# cell_sense_tht.net
KiCad netlist of a schematic drawn in EAGLE
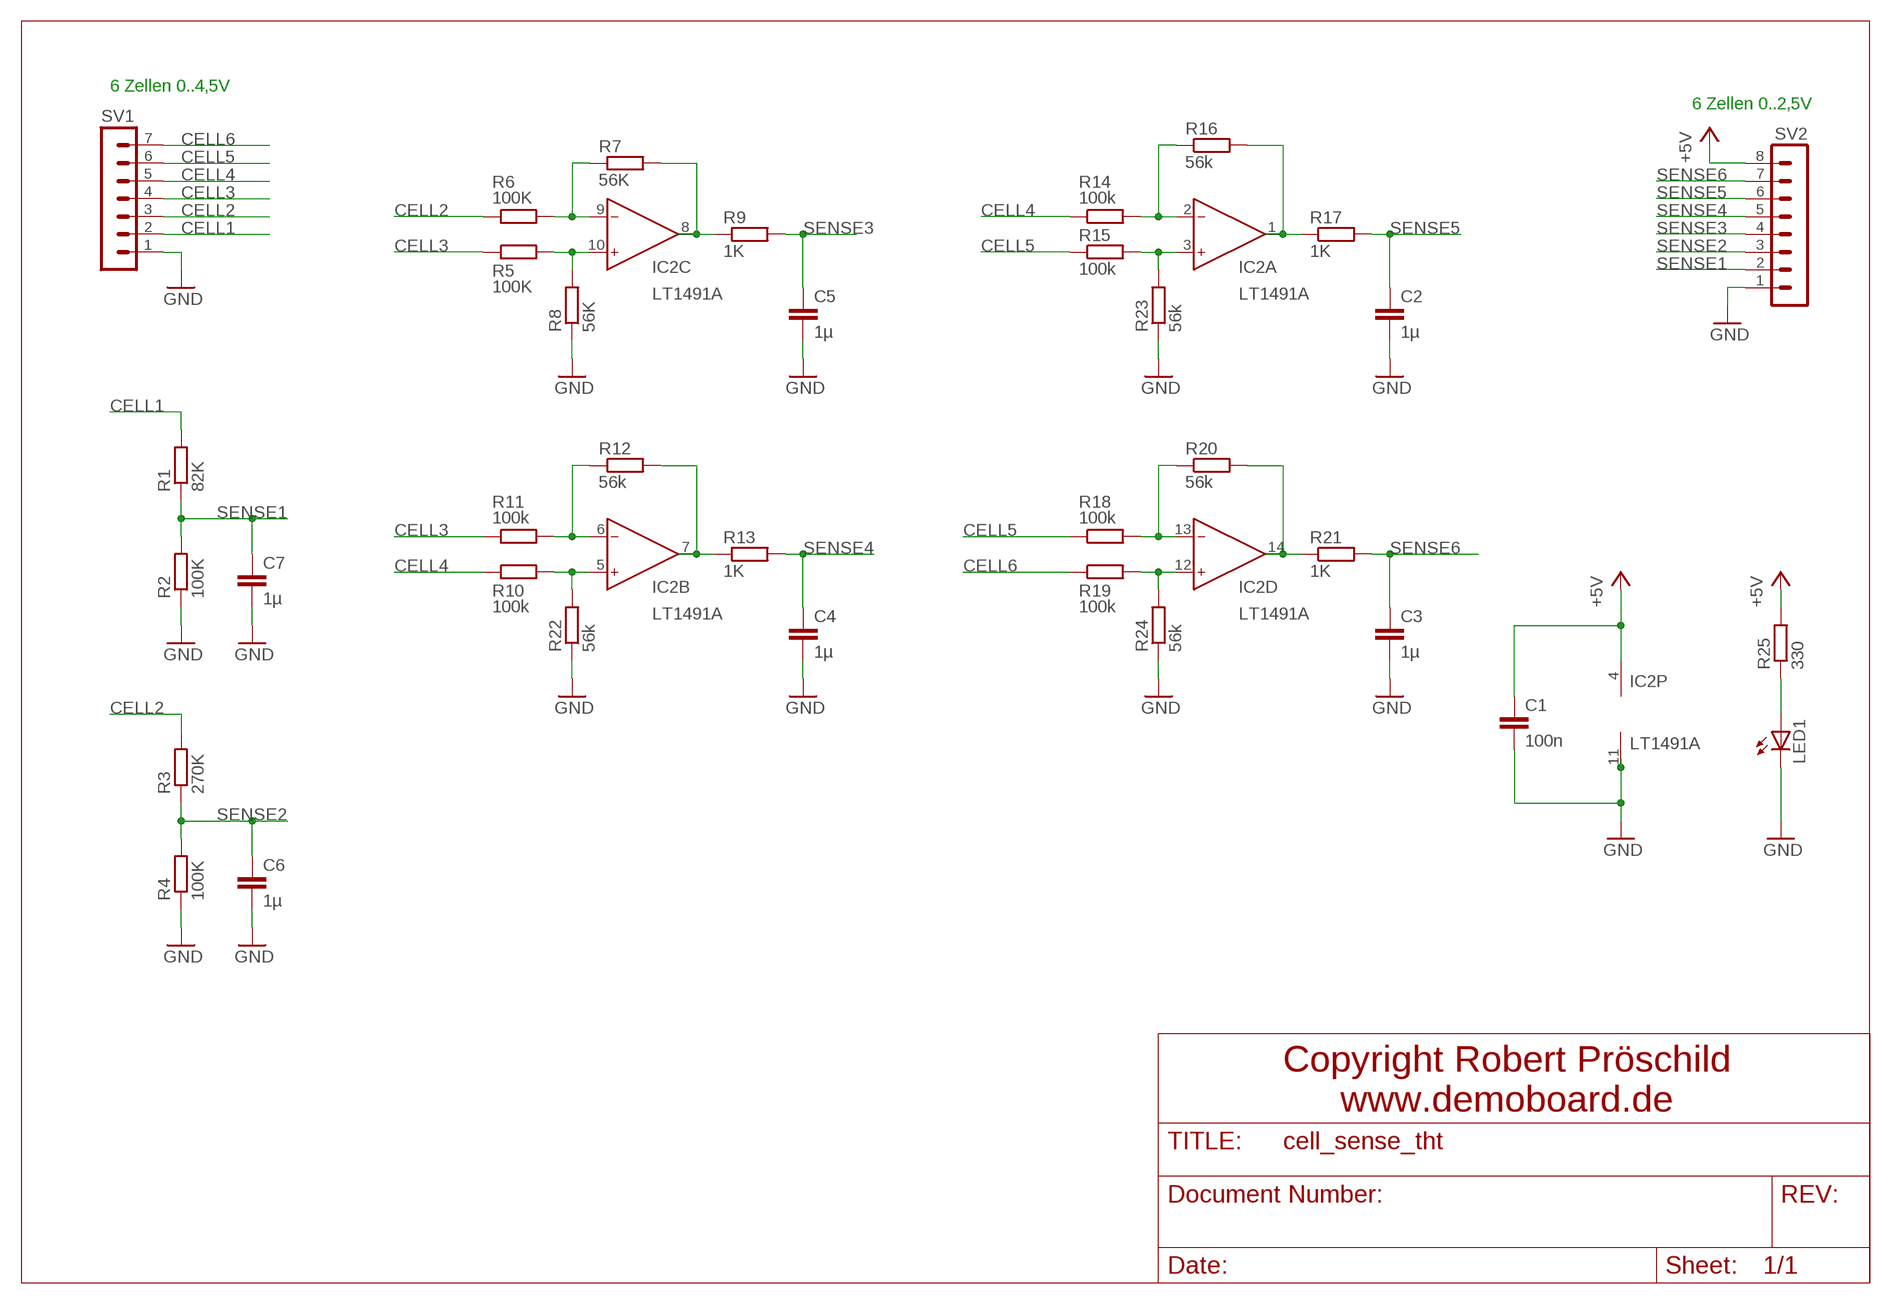
[diagram p0: schematic, sheet 1]

(export (version "E")
  (design (tool "Eeschema 10.0.6"))
  (components
    (comp (ref "C1")
      (value "100n")
      (footprint "eagle-import:C025-024X044")
      (libsource (lib "eagle-import") (part "C-EU025-024X044"))
    )
    (comp (ref "C2")
      (value "1µ")
      (footprint "eagle-import:C025-024X044")
      (libsource (lib "eagle-import") (part "C-EU025-024X044"))
    )
    (comp (ref "C3")
      (value "1µ")
      (footprint "eagle-import:C025-024X044")
      (libsource (lib "eagle-import") (part "C-EU025-024X044"))
    )
    (comp (ref "C4")
      (value "1µ")
      (footprint "eagle-import:C025-024X044")
      (libsource (lib "eagle-import") (part "C-EU025-024X044"))
    )
    (comp (ref "C5")
      (value "1µ")
      (footprint "eagle-import:C025-024X044")
      (libsource (lib "eagle-import") (part "C-EU025-024X044"))
    )
    (comp (ref "C6")
      (value "1µ")
      (footprint "eagle-import:C025-024X044")
      (libsource (lib "eagle-import") (part "C-EU025-024X044"))
    )
    (comp (ref "C7")
      (value "1µ")
      (footprint "eagle-import:C025-024X044")
      (libsource (lib "eagle-import") (part "C-EU025-024X044"))
    )
    (comp (ref "IC2")
      (value "LT1491A")
      (footprint "eagle-import:DIL14")
      (libsource (lib "eagle-import") (part "AD8644"))
    )
    (comp (ref "LED1")
      (value "LED3MM")
      (footprint "eagle-import:LED3MM")
      (libsource (lib "eagle-import") (part "LED3MM"))
    )
    (comp (ref "R1")
      (value "82K")
      (footprint "eagle-import:0204_7")
      (libsource (lib "eagle-import") (part "R-EU_0204/7"))
    )
    (comp (ref "R2")
      (value "100K")
      (footprint "eagle-import:0204_7")
      (libsource (lib "eagle-import") (part "R-EU_0204/7"))
    )
    (comp (ref "R3")
      (value "270K")
      (footprint "eagle-import:0204_7")
      (libsource (lib "eagle-import") (part "R-EU_0204/7"))
    )
    (comp (ref "R4")
      (value "100K")
      (footprint "eagle-import:0204_7")
      (libsource (lib "eagle-import") (part "R-EU_0204/7"))
    )
    (comp (ref "R5")
      (value "100K")
      (footprint "eagle-import:0204_7")
      (libsource (lib "eagle-import") (part "R-EU_0204/7"))
    )
    (comp (ref "R6")
      (value "100K")
      (footprint "eagle-import:0204_7")
      (libsource (lib "eagle-import") (part "R-EU_0204/7"))
    )
    (comp (ref "R7")
      (value "56K")
      (footprint "eagle-import:0204_7")
      (libsource (lib "eagle-import") (part "R-EU_0204/7"))
    )
    (comp (ref "R8")
      (value "56K")
      (footprint "eagle-import:0204_7")
      (libsource (lib "eagle-import") (part "R-EU_0204/7"))
    )
    (comp (ref "R9")
      (value "1K")
      (footprint "eagle-import:0204_7")
      (libsource (lib "eagle-import") (part "R-EU_0204/7"))
    )
    (comp (ref "R10")
      (value "100k")
      (footprint "eagle-import:0204_7")
      (libsource (lib "eagle-import") (part "R-EU_0204/7"))
    )
    (comp (ref "R11")
      (value "100k")
      (footprint "eagle-import:0204_7")
      (libsource (lib "eagle-import") (part "R-EU_0204/7"))
    )
    (comp (ref "R12")
      (value "56k")
      (footprint "eagle-import:0204_7")
      (libsource (lib "eagle-import") (part "R-EU_0204/7"))
    )
    (comp (ref "R13")
      (value "1K")
      (footprint "eagle-import:0204_7")
      (libsource (lib "eagle-import") (part "R-EU_0204/7"))
    )
    (comp (ref "R14")
      (value "100k")
      (footprint "eagle-import:0204_7")
      (libsource (lib "eagle-import") (part "R-EU_0204/7"))
    )
    (comp (ref "R15")
      (value "100k")
      (footprint "eagle-import:0204_7")
      (libsource (lib "eagle-import") (part "R-EU_0204/7"))
    )
    (comp (ref "R16")
      (value "56k")
      (footprint "eagle-import:0204_7")
      (libsource (lib "eagle-import") (part "R-EU_0204/7"))
    )
    (comp (ref "R17")
      (value "1K")
      (footprint "eagle-import:0204_7")
      (libsource (lib "eagle-import") (part "R-EU_0204/7"))
    )
    (comp (ref "R18")
      (value "100k")
      (footprint "eagle-import:0204_7")
      (libsource (lib "eagle-import") (part "R-EU_0204/7"))
    )
    (comp (ref "R19")
      (value "100k")
      (footprint "eagle-import:0204_7")
      (libsource (lib "eagle-import") (part "R-EU_0204/7"))
    )
    (comp (ref "R20")
      (value "56k")
      (footprint "eagle-import:0204_7")
      (libsource (lib "eagle-import") (part "R-EU_0204/7"))
    )
    (comp (ref "R21")
      (value "1K")
      (footprint "eagle-import:0204_7")
      (libsource (lib "eagle-import") (part "R-EU_0204/7"))
    )
    (comp (ref "R22")
      (value "56k")
      (footprint "eagle-import:0204_7")
      (libsource (lib "eagle-import") (part "R-EU_0204/7"))
    )
    (comp (ref "R23")
      (value "56k")
      (footprint "eagle-import:0204_7")
      (libsource (lib "eagle-import") (part "R-EU_0204/7"))
    )
    (comp (ref "R24")
      (value "56k")
      (footprint "eagle-import:0204_7")
      (libsource (lib "eagle-import") (part "R-EU_0204/7"))
    )
    (comp (ref "R25")
      (value "330")
      (footprint "eagle-import:0204_7")
      (libsource (lib "eagle-import") (part "R-EU_0204/7"))
    )
    (comp (ref "SV1")
      (value "MA07-1")
      (footprint "eagle-import:MA07-1")
      (libsource (lib "eagle-import") (part "MA07-1"))
    )
    (comp (ref "SV2")
      (value "MA08-1")
      (footprint "eagle-import:MA08-1")
      (libsource (lib "eagle-import") (part "MA08-1"))
    )
  )
  (nets
    (net (code "1") (name "+5V") (class "Default")
      (node (ref "C1") (pin "1") (pinfunction "1_1") (pintype "passive"))
      (node (ref "IC2") (pin "4") (pinfunction "V+_4") (pintype "power_in"))
      (node (ref "R25") (pin "2") (pinfunction "2_2") (pintype "passive"))
      (node (ref "SV2") (pin "8") (pinfunction "8_8") (pintype "passive"))
    )
    (net (code "2") (name "/CELL1") (class "Default")
      (node (ref "R1") (pin "2") (pinfunction "2_2") (pintype "passive"))
      (node (ref "SV1") (pin "2") (pinfunction "2_2") (pintype "passive"))
    )
    (net (code "3") (name "/CELL2") (class "Default")
      (node (ref "R3") (pin "2") (pinfunction "2_2") (pintype "passive"))
      (node (ref "R6") (pin "1") (pinfunction "1_1") (pintype "passive"))
      (node (ref "SV1") (pin "3") (pinfunction "3_3") (pintype "passive"))
    )
    (net (code "4") (name "/CELL3") (class "Default")
      (node (ref "R11") (pin "1") (pinfunction "1_1") (pintype "passive"))
      (node (ref "R5") (pin "1") (pinfunction "1_1") (pintype "passive"))
      (node (ref "SV1") (pin "4") (pinfunction "4_4") (pintype "passive"))
    )
    (net (code "5") (name "/CELL4") (class "Default")
      (node (ref "R10") (pin "1") (pinfunction "1_1") (pintype "passive"))
      (node (ref "R14") (pin "1") (pinfunction "1_1") (pintype "passive"))
      (node (ref "SV1") (pin "5") (pinfunction "5_5") (pintype "passive"))
    )
    (net (code "6") (name "/CELL5") (class "Default")
      (node (ref "R15") (pin "1") (pinfunction "1_1") (pintype "passive"))
      (node (ref "R18") (pin "1") (pinfunction "1_1") (pintype "passive"))
      (node (ref "SV1") (pin "6") (pinfunction "6_6") (pintype "passive"))
    )
    (net (code "7") (name "/CELL6") (class "Default")
      (node (ref "R19") (pin "1") (pinfunction "1_1") (pintype "passive"))
      (node (ref "SV1") (pin "7") (pinfunction "7_7") (pintype "passive"))
    )
    (net (code "8") (name "/SENSE1") (class "Default")
      (node (ref "C7") (pin "1") (pinfunction "1_1") (pintype "passive"))
      (node (ref "R1") (pin "1") (pinfunction "1_1") (pintype "passive"))
      (node (ref "R2") (pin "2") (pinfunction "2_2") (pintype "passive"))
      (node (ref "SV2") (pin "2") (pinfunction "2_2") (pintype "passive"))
    )
    (net (code "9") (name "/SENSE2") (class "Default")
      (node (ref "C6") (pin "1") (pinfunction "1_1") (pintype "passive"))
      (node (ref "R3") (pin "1") (pinfunction "1_1") (pintype "passive"))
      (node (ref "R4") (pin "2") (pinfunction "2_2") (pintype "passive"))
      (node (ref "SV2") (pin "3") (pinfunction "3_3") (pintype "passive"))
    )
    (net (code "10") (name "/SENSE3") (class "Default")
      (node (ref "C5") (pin "1") (pinfunction "1_1") (pintype "passive"))
      (node (ref "R9") (pin "2") (pinfunction "2_2") (pintype "passive"))
      (node (ref "SV2") (pin "4") (pinfunction "4_4") (pintype "passive"))
    )
    (net (code "11") (name "/SENSE4") (class "Default")
      (node (ref "C4") (pin "1") (pinfunction "1_1") (pintype "passive"))
      (node (ref "R13") (pin "2") (pinfunction "2_2") (pintype "passive"))
      (node (ref "SV2") (pin "5") (pinfunction "5_5") (pintype "passive"))
    )
    (net (code "12") (name "/SENSE5") (class "Default")
      (node (ref "C2") (pin "1") (pinfunction "1_1") (pintype "passive"))
      (node (ref "R17") (pin "2") (pinfunction "2_2") (pintype "passive"))
      (node (ref "SV2") (pin "6") (pinfunction "6_6") (pintype "passive"))
    )
    (net (code "13") (name "/SENSE6") (class "Default")
      (node (ref "C3") (pin "1") (pinfunction "1_1") (pintype "passive"))
      (node (ref "R21") (pin "2") (pinfunction "2_2") (pintype "passive"))
      (node (ref "SV2") (pin "7") (pinfunction "7_7") (pintype "passive"))
    )
    (net (code "14") (name "GND") (class "Default")
      (node (ref "C1") (pin "2") (pinfunction "2_2") (pintype "passive"))
      (node (ref "C2") (pin "2") (pinfunction "2_2") (pintype "passive"))
      (node (ref "C3") (pin "2") (pinfunction "2_2") (pintype "passive"))
      (node (ref "C4") (pin "2") (pinfunction "2_2") (pintype "passive"))
      (node (ref "C5") (pin "2") (pinfunction "2_2") (pintype "passive"))
      (node (ref "C6") (pin "2") (pinfunction "2_2") (pintype "passive"))
      (node (ref "C7") (pin "2") (pinfunction "2_2") (pintype "passive"))
      (node (ref "IC2") (pin "11") (pinfunction "V-_11") (pintype "power_in"))
      (node (ref "LED1") (pin "K") (pinfunction "C_K") (pintype "passive"))
      (node (ref "R2") (pin "1") (pinfunction "1_1") (pintype "passive"))
      (node (ref "R22") (pin "1") (pinfunction "1_1") (pintype "passive"))
      (node (ref "R23") (pin "1") (pinfunction "1_1") (pintype "passive"))
      (node (ref "R24") (pin "1") (pinfunction "1_1") (pintype "passive"))
      (node (ref "R4") (pin "1") (pinfunction "1_1") (pintype "passive"))
      (node (ref "R8") (pin "1") (pinfunction "1_1") (pintype "passive"))
      (node (ref "SV1") (pin "1") (pinfunction "1_1") (pintype "passive"))
      (node (ref "SV2") (pin "1") (pinfunction "1_1") (pintype "passive"))
    )
    (net (code "15") (name "Net-(IC2A-IN+)") (class "Default")
      (node (ref "IC2") (pin "3") (pinfunction "IN+_3") (pintype "input"))
      (node (ref "R15") (pin "2") (pinfunction "2_2") (pintype "passive"))
      (node (ref "R23") (pin "2") (pinfunction "2_2") (pintype "passive"))
    )
    (net (code "16") (name "Net-(IC2A-IN-)") (class "Default")
      (node (ref "IC2") (pin "2") (pinfunction "IN-_2") (pintype "input"))
      (node (ref "R14") (pin "2") (pinfunction "2_2") (pintype "passive"))
      (node (ref "R16") (pin "1") (pinfunction "1_1") (pintype "passive"))
    )
    (net (code "17") (name "Net-(IC2A-OUT)") (class "Default")
      (node (ref "IC2") (pin "1") (pinfunction "OUT_1") (pintype "output"))
      (node (ref "R16") (pin "2") (pinfunction "2_2") (pintype "passive"))
      (node (ref "R17") (pin "1") (pinfunction "1_1") (pintype "passive"))
    )
    (net (code "18") (name "Net-(IC2B-IN+)") (class "Default")
      (node (ref "IC2") (pin "5") (pinfunction "IN+_5") (pintype "input"))
      (node (ref "R10") (pin "2") (pinfunction "2_2") (pintype "passive"))
      (node (ref "R22") (pin "2") (pinfunction "2_2") (pintype "passive"))
    )
    (net (code "19") (name "Net-(IC2B-IN-)") (class "Default")
      (node (ref "IC2") (pin "6") (pinfunction "IN-_6") (pintype "input"))
      (node (ref "R11") (pin "2") (pinfunction "2_2") (pintype "passive"))
      (node (ref "R12") (pin "1") (pinfunction "1_1") (pintype "passive"))
    )
    (net (code "20") (name "Net-(IC2B-OUT)") (class "Default")
      (node (ref "IC2") (pin "7") (pinfunction "OUT_7") (pintype "output"))
      (node (ref "R12") (pin "2") (pinfunction "2_2") (pintype "passive"))
      (node (ref "R13") (pin "1") (pinfunction "1_1") (pintype "passive"))
    )
    (net (code "21") (name "Net-(IC2C-IN+)") (class "Default")
      (node (ref "IC2") (pin "10") (pinfunction "IN+_10") (pintype "input"))
      (node (ref "R5") (pin "2") (pinfunction "2_2") (pintype "passive"))
      (node (ref "R8") (pin "2") (pinfunction "2_2") (pintype "passive"))
    )
    (net (code "22") (name "Net-(IC2C-IN-)") (class "Default")
      (node (ref "IC2") (pin "9") (pinfunction "IN-_9") (pintype "input"))
      (node (ref "R6") (pin "2") (pinfunction "2_2") (pintype "passive"))
      (node (ref "R7") (pin "1") (pinfunction "1_1") (pintype "passive"))
    )
    (net (code "23") (name "Net-(IC2C-OUT)") (class "Default")
      (node (ref "IC2") (pin "8") (pinfunction "OUT_8") (pintype "output"))
      (node (ref "R7") (pin "2") (pinfunction "2_2") (pintype "passive"))
      (node (ref "R9") (pin "1") (pinfunction "1_1") (pintype "passive"))
    )
    (net (code "24") (name "Net-(IC2D-IN+)") (class "Default")
      (node (ref "IC2") (pin "12") (pinfunction "IN+_12") (pintype "input"))
      (node (ref "R19") (pin "2") (pinfunction "2_2") (pintype "passive"))
      (node (ref "R24") (pin "2") (pinfunction "2_2") (pintype "passive"))
    )
    (net (code "25") (name "Net-(IC2D-IN-)") (class "Default")
      (node (ref "IC2") (pin "13") (pinfunction "IN-_13") (pintype "input"))
      (node (ref "R18") (pin "2") (pinfunction "2_2") (pintype "passive"))
      (node (ref "R20") (pin "1") (pinfunction "1_1") (pintype "passive"))
    )
    (net (code "26") (name "Net-(IC2D-OUT)") (class "Default")
      (node (ref "IC2") (pin "14") (pinfunction "OUT_14") (pintype "output"))
      (node (ref "R20") (pin "2") (pinfunction "2_2") (pintype "passive"))
      (node (ref "R21") (pin "1") (pinfunction "1_1") (pintype "passive"))
    )
    (net (code "27") (name "Net-(LED1-PadA)") (class "Default")
      (node (ref "LED1") (pin "A") (pinfunction "A_A") (pintype "passive"))
      (node (ref "R25") (pin "1") (pinfunction "1_1") (pintype "passive"))
    )
  )
)
